# subor.net
KiCad netlist of a schematic drawn in EAGLE
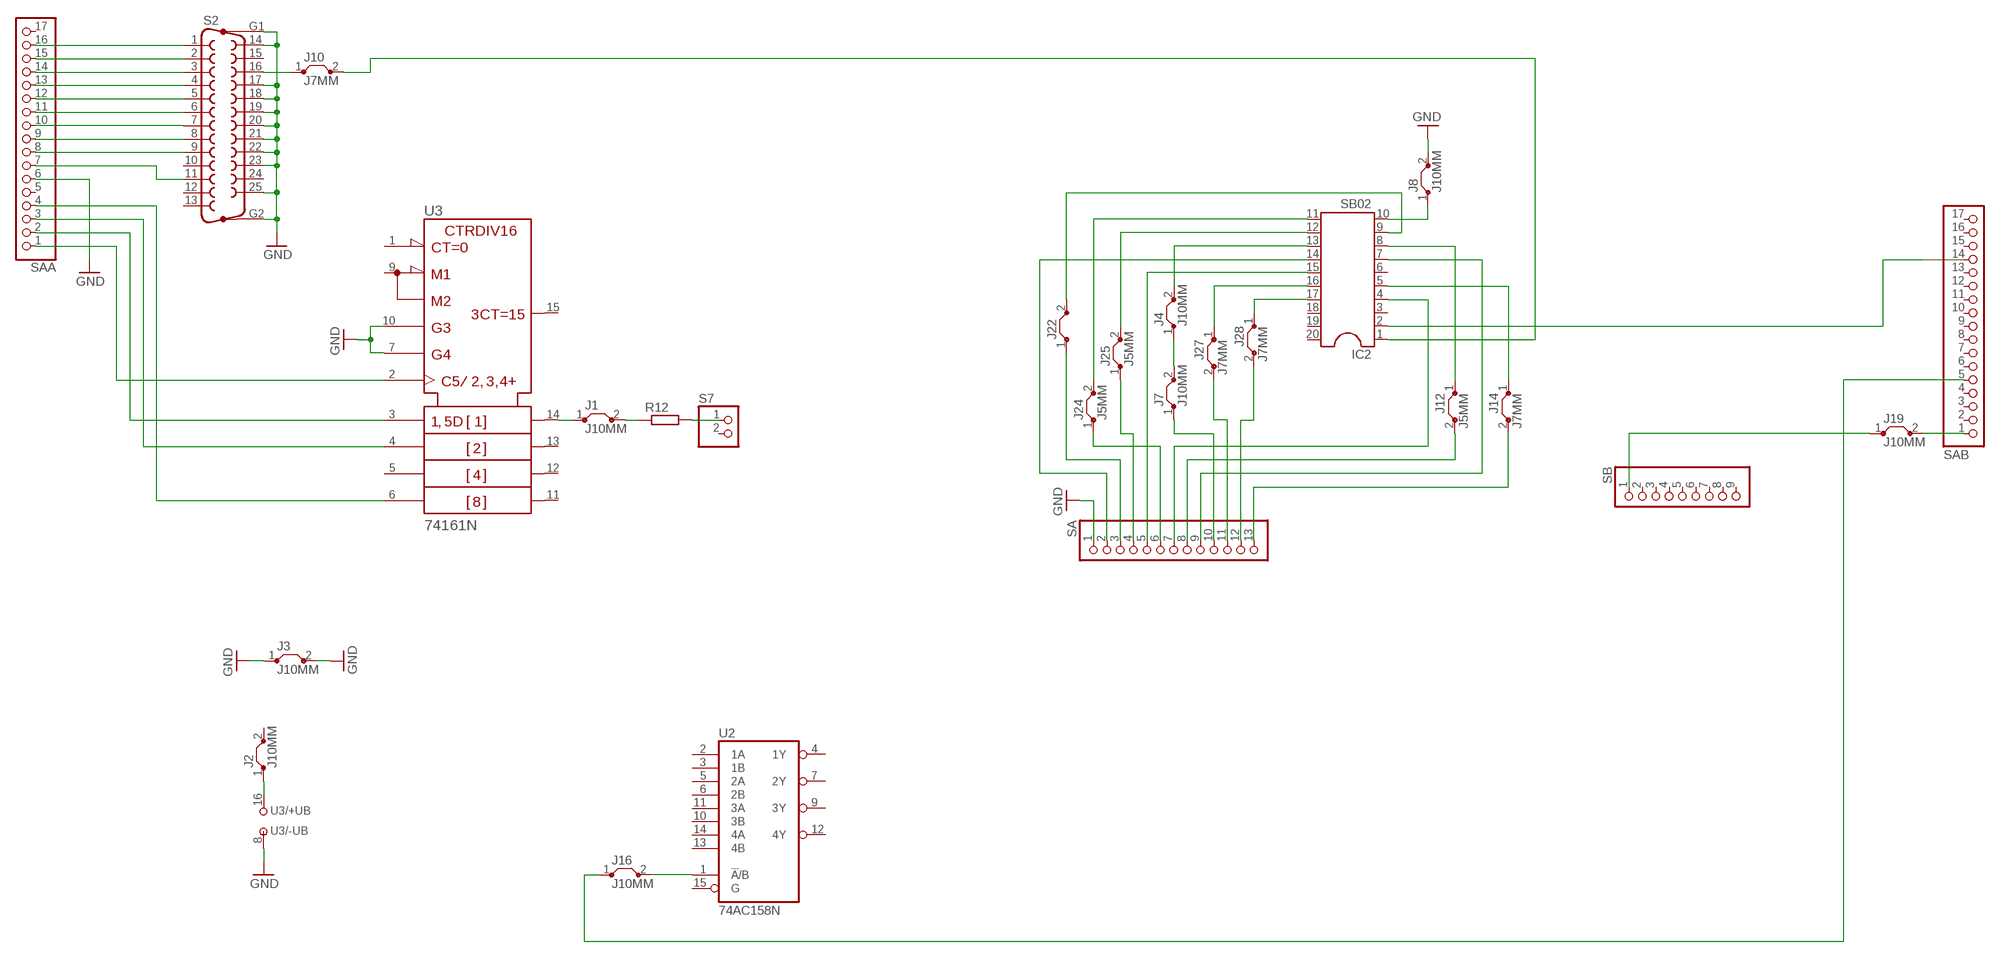
[diagram p0: schematic, sheet 1]

(export (version "E")
  (design (tool "Eeschema 10.0.6"))
  (components
    (comp (ref "IC2")
      (value "SB02")
      (footprint "eagle-import:DIL20")
      (libsource (lib "eagle-import") (part "DIL20"))
    )
    (comp (ref "J1")
      (value "J10MM")
      (footprint "eagle-import:10")
      (libsource (lib "eagle-import") (part "J10MM"))
    )
    (comp (ref "J2")
      (value "J10MM")
      (footprint "eagle-import:10")
      (libsource (lib "eagle-import") (part "J10MM"))
    )
    (comp (ref "J3")
      (value "J10MM")
      (footprint "eagle-import:10")
      (libsource (lib "eagle-import") (part "J10MM"))
    )
    (comp (ref "J4")
      (value "J10MM")
      (footprint "eagle-import:10")
      (libsource (lib "eagle-import") (part "J10MM"))
    )
    (comp (ref "J7")
      (value "J10MM")
      (footprint "eagle-import:10")
      (libsource (lib "eagle-import") (part "J10MM"))
    )
    (comp (ref "J8")
      (value "J10MM")
      (footprint "eagle-import:10")
      (libsource (lib "eagle-import") (part "J10MM"))
    )
    (comp (ref "J10")
      (value "J7MM")
      (footprint "eagle-import:07")
      (libsource (lib "eagle-import") (part "J7MM"))
    )
    (comp (ref "J12")
      (value "J5MM")
      (footprint "eagle-import:05")
      (libsource (lib "eagle-import") (part "J5MM"))
    )
    (comp (ref "J14")
      (value "J7MM")
      (footprint "eagle-import:07")
      (libsource (lib "eagle-import") (part "J7MM"))
    )
    (comp (ref "J16")
      (value "J10MM")
      (footprint "eagle-import:10")
      (libsource (lib "eagle-import") (part "J10MM"))
    )
    (comp (ref "J19")
      (value "J10MM")
      (footprint "eagle-import:10")
      (libsource (lib "eagle-import") (part "J10MM"))
    )
    (comp (ref "J22")
      (value "J10MM")
      (footprint "eagle-import:10")
      (libsource (lib "eagle-import") (part "J10MM"))
    )
    (comp (ref "J24")
      (value "J5MM")
      (footprint "eagle-import:05")
      (libsource (lib "eagle-import") (part "J5MM"))
    )
    (comp (ref "J25")
      (value "J5MM")
      (footprint "eagle-import:05")
      (libsource (lib "eagle-import") (part "J5MM"))
    )
    (comp (ref "J27")
      (value "J7MM")
      (footprint "eagle-import:07")
      (libsource (lib "eagle-import") (part "J7MM"))
    )
    (comp (ref "J28")
      (value "J7MM")
      (footprint "eagle-import:07")
      (libsource (lib "eagle-import") (part "J7MM"))
    )
    (comp (ref "R12")
      (value "R-EU_0207/10")
      (footprint "eagle-import:0207_10")
      (libsource (lib "eagle-import") (part "R-EU_0207/10"))
    )
    (comp (ref "S2")
      (value "F25HP")
      (footprint "eagle-import:F25HP")
      (libsource (lib "eagle-import") (part "F25HP"))
    )
    (comp (ref "S7")
      (value "PINHD-1X2")
      (footprint "eagle-import:1X02")
      (libsource (lib "eagle-import") (part "PINHD-1X2"))
    )
    (comp (ref "SA")
      (value "PINHD-1X13/90")
      (footprint "eagle-import:1X13_90")
      (libsource (lib "eagle-import") (part "PINHD-1X13/90"))
    )
    (comp (ref "SAA")
      (value "PINHD-1X17")
      (footprint "eagle-import:1X17")
      (libsource (lib "eagle-import") (part "PINHD-1X17"))
    )
    (comp (ref "SAB")
      (value "PINHD-1X17")
      (footprint "eagle-import:1X17")
      (libsource (lib "eagle-import") (part "PINHD-1X17"))
    )
    (comp (ref "SB")
      (value "PINHD-1X9/90")
      (footprint "eagle-import:1X09_90")
      (libsource (lib "eagle-import") (part "PINHD-1X9/90"))
    )
    (comp (ref "U2")
      (value "74AC158N")
      (footprint "eagle-import:DIL16")
      (libsource (lib "eagle-import") (part "74158NAC"))
    )
    (comp (ref "U3")
      (value "74161N")
      (footprint "eagle-import:DIL16")
      (libsource (lib "eagle-import") (part "74161N"))
    )
  )
  (nets
    (net (code "1") (name "GND") (class "Default")
      (node (ref "J3") (pin "1") (pinfunction "1_1") (pintype "passive"))
      (node (ref "J3") (pin "2") (pinfunction "2_2") (pintype "passive"))
      (node (ref "J8") (pin "2") (pinfunction "2_2") (pintype "passive"))
      (node (ref "S2") (pin "14") (pinfunction "14_14") (pintype "passive"))
      (node (ref "S2") (pin "17") (pinfunction "17_17") (pintype "passive"))
      (node (ref "S2") (pin "18") (pinfunction "18_18") (pintype "passive"))
      (node (ref "S2") (pin "19") (pinfunction "19_19") (pintype "passive"))
      (node (ref "S2") (pin "20") (pinfunction "20_20") (pintype "passive"))
      (node (ref "S2") (pin "21") (pinfunction "21_21") (pintype "passive"))
      (node (ref "S2") (pin "22") (pinfunction "22_22") (pintype "passive"))
      (node (ref "S2") (pin "23") (pinfunction "23_23") (pintype "passive"))
      (node (ref "S2") (pin "25") (pinfunction "25_25") (pintype "passive"))
      (node (ref "S2") (pin "G1") (pinfunction "G1_G1") (pintype "passive"))
      (node (ref "S2") (pin "G2") (pinfunction "G2_G2") (pintype "passive"))
      (node (ref "SA") (pin "1") (pinfunction "1_1") (pintype "passive"))
      (node (ref "SAA") (pin "6") (pinfunction "6_6") (pintype "passive"))
      (node (ref "U3") (pin "10") (pinfunction "ENT_10") (pintype "input"))
      (node (ref "U3") (pin "7") (pinfunction "ENP_7") (pintype "input"))
      (node (ref "U3") (pin "8") (pinfunction "-UB_8") (pintype "power_in"))
    )
    (net (code "2") (name "Net-(IC2-Pad1)") (class "Default")
      (node (ref "IC2") (pin "1") (pinfunction "1_1") (pintype "passive"))
      (node (ref "J10") (pin "2") (pinfunction "2_2") (pintype "passive"))
    )
    (net (code "3") (name "Net-(IC2-Pad4)") (class "Default")
      (node (ref "IC2") (pin "4") (pinfunction "4_4") (pintype "passive"))
      (node (ref "SA") (pin "7") (pinfunction "7_7") (pintype "passive"))
    )
    (net (code "4") (name "Net-(IC2-Pad5)") (class "Default")
      (node (ref "IC2") (pin "5") (pinfunction "5_5") (pintype "passive"))
      (node (ref "J14") (pin "1") (pinfunction "1_1") (pintype "passive"))
    )
    (net (code "5") (name "Net-(IC2-Pad7)") (class "Default")
      (node (ref "IC2") (pin "7") (pinfunction "7_7") (pintype "passive"))
      (node (ref "SA") (pin "9") (pinfunction "9_9") (pintype "passive"))
    )
    (net (code "6") (name "Net-(IC2-Pad8)") (class "Default")
      (node (ref "IC2") (pin "8") (pinfunction "8_8") (pintype "passive"))
      (node (ref "J12") (pin "1") (pinfunction "1_1") (pintype "passive"))
    )
    (net (code "7") (name "Net-(IC2-Pad9)") (class "Default")
      (node (ref "IC2") (pin "9") (pinfunction "9_9") (pintype "passive"))
      (node (ref "J22") (pin "2") (pinfunction "2_2") (pintype "passive"))
    )
    (net (code "8") (name "Net-(IC2-Pad10)") (class "Default")
      (node (ref "IC2") (pin "10") (pinfunction "10_10") (pintype "passive"))
      (node (ref "J8") (pin "1") (pinfunction "1_1") (pintype "passive"))
    )
    (net (code "9") (name "Net-(IC2-Pad11)") (class "Default")
      (node (ref "IC2") (pin "11") (pinfunction "11_11") (pintype "passive"))
      (node (ref "J24") (pin "2") (pinfunction "2_2") (pintype "passive"))
    )
    (net (code "10") (name "Net-(IC2-Pad12)") (class "Default")
      (node (ref "IC2") (pin "12") (pinfunction "12_12") (pintype "passive"))
      (node (ref "J25") (pin "2") (pinfunction "2_2") (pintype "passive"))
    )
    (net (code "11") (name "Net-(IC2-Pad13)") (class "Default")
      (node (ref "IC2") (pin "13") (pinfunction "13_13") (pintype "passive"))
      (node (ref "J4") (pin "2") (pinfunction "2_2") (pintype "passive"))
    )
    (net (code "12") (name "Net-(IC2-Pad14)") (class "Default")
      (node (ref "IC2") (pin "14") (pinfunction "14_14") (pintype "passive"))
      (node (ref "SA") (pin "2") (pinfunction "2_2") (pintype "passive"))
    )
    (net (code "13") (name "Net-(IC2-Pad15)") (class "Default")
      (node (ref "IC2") (pin "15") (pinfunction "15_15") (pintype "passive"))
      (node (ref "SA") (pin "5") (pinfunction "5_5") (pintype "passive"))
    )
    (net (code "14") (name "Net-(IC2-Pad16)") (class "Default")
      (node (ref "IC2") (pin "16") (pinfunction "16_16") (pintype "passive"))
      (node (ref "J27") (pin "1") (pinfunction "1_1") (pintype "passive"))
    )
    (net (code "15") (name "Net-(IC2-Pad17)") (class "Default")
      (node (ref "IC2") (pin "17") (pinfunction "17_17") (pintype "passive"))
      (node (ref "J28") (pin "1") (pinfunction "1_1") (pintype "passive"))
    )
    (net (code "16") (name "Net-(J1-Pad2)") (class "Default")
      (node (ref "J1") (pin "2") (pinfunction "2_2") (pintype "passive"))
      (node (ref "R12") (pin "1") (pinfunction "1_1") (pintype "passive"))
    )
    (net (code "17") (name "Net-(J4-Pad1)") (class "Default")
      (node (ref "J4") (pin "1") (pinfunction "1_1") (pintype "passive"))
      (node (ref "J7") (pin "2") (pinfunction "2_2") (pintype "passive"))
    )
    (net (code "18") (name "Net-(J7-Pad1)") (class "Default")
      (node (ref "J7") (pin "1") (pinfunction "1_1") (pintype "passive"))
      (node (ref "SA") (pin "10") (pinfunction "10_10") (pintype "passive"))
    )
    (net (code "19") (name "Net-(J10-Pad1)") (class "Default")
      (node (ref "J10") (pin "1") (pinfunction "1_1") (pintype "passive"))
      (node (ref "S2") (pin "16") (pinfunction "16_16") (pintype "passive"))
    )
    (net (code "20") (name "Net-(J12-Pad2)") (class "Default")
      (node (ref "J12") (pin "2") (pinfunction "2_2") (pintype "passive"))
      (node (ref "SA") (pin "8") (pinfunction "8_8") (pintype "passive"))
    )
    (net (code "21") (name "Net-(J14-Pad2)") (class "Default")
      (node (ref "J14") (pin "2") (pinfunction "2_2") (pintype "passive"))
      (node (ref "SA") (pin "13") (pinfunction "13_13") (pintype "passive"))
    )
    (net (code "22") (name "Net-(J16-Pad1)") (class "Default")
      (node (ref "J16") (pin "1") (pinfunction "1_1") (pintype "passive"))
      (node (ref "SAB") (pin "5") (pinfunction "5_5") (pintype "passive"))
    )
    (net (code "23") (name "Net-(J19-Pad1)") (class "Default")
      (node (ref "J19") (pin "1") (pinfunction "1_1") (pintype "passive"))
      (node (ref "SB") (pin "1") (pinfunction "1_1") (pintype "passive"))
    )
    (net (code "24") (name "Net-(J19-Pad2)") (class "Default")
      (node (ref "J19") (pin "2") (pinfunction "2_2") (pintype "passive"))
      (node (ref "SAB") (pin "1") (pinfunction "1_1") (pintype "passive"))
    )
    (net (code "25") (name "Net-(J22-Pad1)") (class "Default")
      (node (ref "J22") (pin "1") (pinfunction "1_1") (pintype "passive"))
      (node (ref "SA") (pin "3") (pinfunction "3_3") (pintype "passive"))
    )
    (net (code "26") (name "Net-(J24-Pad1)") (class "Default")
      (node (ref "J24") (pin "1") (pinfunction "1_1") (pintype "passive"))
      (node (ref "SA") (pin "6") (pinfunction "6_6") (pintype "passive"))
    )
    (net (code "27") (name "Net-(J25-Pad1)") (class "Default")
      (node (ref "J25") (pin "1") (pinfunction "1_1") (pintype "passive"))
      (node (ref "SA") (pin "4") (pinfunction "4_4") (pintype "passive"))
    )
    (net (code "28") (name "Net-(J27-Pad2)") (class "Default")
      (node (ref "J27") (pin "2") (pinfunction "2_2") (pintype "passive"))
      (node (ref "SA") (pin "11") (pinfunction "11_11") (pintype "passive"))
    )
    (net (code "29") (name "Net-(J28-Pad2)") (class "Default")
      (node (ref "J28") (pin "2") (pinfunction "2_2") (pintype "passive"))
      (node (ref "SA") (pin "12") (pinfunction "12_12") (pintype "passive"))
    )
    (net (code "30") (name "Net-(R12-Pad2)") (class "Default")
      (node (ref "R12") (pin "2") (pinfunction "2_2") (pintype "passive"))
      (node (ref "S7") (pin "1") (pinfunction "1_1") (pintype "passive"))
    )
    (net (code "31") (name "Net-(S2-Pad1)") (class "Default")
      (node (ref "S2") (pin "1") (pinfunction "1_1") (pintype "passive"))
      (node (ref "SAA") (pin "16") (pinfunction "16_16") (pintype "passive"))
    )
    (net (code "32") (name "Net-(S2-Pad2)") (class "Default")
      (node (ref "S2") (pin "2") (pinfunction "2_2") (pintype "passive"))
      (node (ref "SAA") (pin "15") (pinfunction "15_15") (pintype "passive"))
    )
    (net (code "33") (name "Net-(S2-Pad3)") (class "Default")
      (node (ref "S2") (pin "3") (pinfunction "3_3") (pintype "passive"))
      (node (ref "SAA") (pin "14") (pinfunction "14_14") (pintype "passive"))
    )
    (net (code "34") (name "Net-(S2-Pad4)") (class "Default")
      (node (ref "S2") (pin "4") (pinfunction "4_4") (pintype "passive"))
      (node (ref "SAA") (pin "13") (pinfunction "13_13") (pintype "passive"))
    )
    (net (code "35") (name "Net-(S2-Pad5)") (class "Default")
      (node (ref "S2") (pin "5") (pinfunction "5_5") (pintype "passive"))
      (node (ref "SAA") (pin "12") (pinfunction "12_12") (pintype "passive"))
    )
    (net (code "36") (name "Net-(S2-Pad6)") (class "Default")
      (node (ref "S2") (pin "6") (pinfunction "6_6") (pintype "passive"))
      (node (ref "SAA") (pin "11") (pinfunction "11_11") (pintype "passive"))
    )
    (net (code "37") (name "Net-(S2-Pad7)") (class "Default")
      (node (ref "S2") (pin "7") (pinfunction "7_7") (pintype "passive"))
      (node (ref "SAA") (pin "10") (pinfunction "10_10") (pintype "passive"))
    )
    (net (code "38") (name "Net-(S2-Pad8)") (class "Default")
      (node (ref "S2") (pin "8") (pinfunction "8_8") (pintype "passive"))
      (node (ref "SAA") (pin "9") (pinfunction "9_9") (pintype "passive"))
    )
    (net (code "39") (name "Net-(S2-Pad9)") (class "Default")
      (node (ref "S2") (pin "9") (pinfunction "9_9") (pintype "passive"))
      (node (ref "SAA") (pin "8") (pinfunction "8_8") (pintype "passive"))
    )
    (net (code "40") (name "Net-(S2-Pad11)") (class "Default")
      (node (ref "S2") (pin "11") (pinfunction "11_11") (pintype "passive"))
      (node (ref "SAA") (pin "7") (pinfunction "7_7") (pintype "passive"))
    )
    (net (code "41") (name "Net-(U2A-~{A}{slash}B)") (class "Default")
      (node (ref "J16") (pin "2") (pinfunction "2_2") (pintype "passive"))
      (node (ref "U2") (pin "1") (pinfunction "~{A}/B_1") (pintype "input"))
    )
    (net (code "42") (name "Net-(U3A-+UB)") (class "Default")
      (node (ref "J2") (pin "1") (pinfunction "1_1") (pintype "passive"))
      (node (ref "U3") (pin "16") (pinfunction "+UB_16") (pintype "power_in"))
    )
    (net (code "43") (name "Net-(U3C-A)") (class "Default")
      (node (ref "SAA") (pin "2") (pinfunction "2_2") (pintype "passive"))
      (node (ref "U3") (pin "3") (pinfunction "A_3") (pintype "input"))
    )
    (net (code "44") (name "Net-(U3C-B)") (class "Default")
      (node (ref "SAA") (pin "3") (pinfunction "3_3") (pintype "passive"))
      (node (ref "U3") (pin "4") (pinfunction "B_4") (pintype "input"))
    )
    (net (code "45") (name "Net-(U3C-CLK)") (class "Default")
      (node (ref "SAA") (pin "1") (pinfunction "1_1") (pintype "passive"))
      (node (ref "U3") (pin "2") (pinfunction "CLK_2") (pintype "input"))
    )
    (net (code "46") (name "Net-(U3C-D)") (class "Default")
      (node (ref "SAA") (pin "4") (pinfunction "4_4") (pintype "passive"))
      (node (ref "U3") (pin "6") (pinfunction "D_6") (pintype "input"))
    )
    (net (code "47") (name "Net-(U3C-QA)") (class "Default")
      (node (ref "J1") (pin "1") (pinfunction "1_1") (pintype "passive"))
      (node (ref "U3") (pin "14") (pinfunction "QA_14") (pintype "output"))
    )
    (net (code "48") (name "unconnected-(IC2-Pad2)") (class "Default")
      (node (ref "IC2") (pin "2") (pinfunction "2_2") (pintype "passive"))
    )
    (net (code "49") (name "unconnected-(IC2-Pad3)") (class "Default")
      (node (ref "IC2") (pin "3") (pinfunction "3_3") (pintype "passive"))
    )
    (net (code "50") (name "unconnected-(IC2-Pad6)") (class "Default")
      (node (ref "IC2") (pin "6") (pinfunction "6_6") (pintype "passive"))
    )
    (net (code "51") (name "unconnected-(IC2-Pad18)") (class "Default")
      (node (ref "IC2") (pin "18") (pinfunction "18_18") (pintype "passive"))
    )
    (net (code "52") (name "unconnected-(IC2-Pad19)") (class "Default")
      (node (ref "IC2") (pin "19") (pinfunction "19_19") (pintype "passive"))
    )
    (net (code "53") (name "unconnected-(IC2-Pad20)") (class "Default")
      (node (ref "IC2") (pin "20") (pinfunction "20_20") (pintype "passive"))
    )
    (net (code "54") (name "unconnected-(J2-Pad2)") (class "Default")
      (node (ref "J2") (pin "2") (pinfunction "2_2") (pintype "passive"))
    )
    (net (code "55") (name "unconnected-(S2-Pad10)") (class "Default")
      (node (ref "S2") (pin "10") (pinfunction "10_10") (pintype "passive"))
    )
    (net (code "56") (name "unconnected-(S2-Pad12)") (class "Default")
      (node (ref "S2") (pin "12") (pinfunction "12_12") (pintype "passive"))
    )
    (net (code "57") (name "unconnected-(S2-Pad13)") (class "Default")
      (node (ref "S2") (pin "13") (pinfunction "13_13") (pintype "passive"))
    )
    (net (code "58") (name "unconnected-(S2-Pad15)") (class "Default")
      (node (ref "S2") (pin "15") (pinfunction "15_15") (pintype "passive"))
    )
    (net (code "59") (name "unconnected-(S2-Pad24)") (class "Default")
      (node (ref "S2") (pin "24") (pinfunction "24_24") (pintype "passive"))
    )
    (net (code "60") (name "unconnected-(S7-Pad2)") (class "Default")
      (node (ref "S7") (pin "2") (pinfunction "2_2") (pintype "passive"))
    )
    (net (code "61") (name "unconnected-(SAA-Pad5)") (class "Default")
      (node (ref "SAA") (pin "5") (pinfunction "5_5") (pintype "passive"))
    )
    (net (code "62") (name "unconnected-(SAA-Pad17)") (class "Default")
      (node (ref "SAA") (pin "17") (pinfunction "17_17") (pintype "passive"))
    )
    (net (code "63") (name "unconnected-(SAB-Pad2)") (class "Default")
      (node (ref "SAB") (pin "2") (pinfunction "2_2") (pintype "passive"))
    )
    (net (code "64") (name "unconnected-(SAB-Pad3)") (class "Default")
      (node (ref "SAB") (pin "3") (pinfunction "3_3") (pintype "passive"))
    )
    (net (code "65") (name "unconnected-(SAB-Pad4)") (class "Default")
      (node (ref "SAB") (pin "4") (pinfunction "4_4") (pintype "passive"))
    )
    (net (code "66") (name "unconnected-(SAB-Pad6)") (class "Default")
      (node (ref "SAB") (pin "6") (pinfunction "6_6") (pintype "passive"))
    )
    (net (code "67") (name "unconnected-(SAB-Pad7)") (class "Default")
      (node (ref "SAB") (pin "7") (pinfunction "7_7") (pintype "passive"))
    )
    (net (code "68") (name "unconnected-(SAB-Pad8)") (class "Default")
      (node (ref "SAB") (pin "8") (pinfunction "8_8") (pintype "passive"))
    )
    (net (code "69") (name "unconnected-(SAB-Pad9)") (class "Default")
      (node (ref "SAB") (pin "9") (pinfunction "9_9") (pintype "passive"))
    )
    (net (code "70") (name "unconnected-(SAB-Pad10)") (class "Default")
      (node (ref "SAB") (pin "10") (pinfunction "10_10") (pintype "passive"))
    )
    (net (code "71") (name "unconnected-(SAB-Pad11)") (class "Default")
      (node (ref "SAB") (pin "11") (pinfunction "11_11") (pintype "passive"))
    )
    (net (code "72") (name "unconnected-(SAB-Pad12)") (class "Default")
      (node (ref "SAB") (pin "12") (pinfunction "12_12") (pintype "passive"))
    )
    (net (code "73") (name "unconnected-(SAB-Pad13)") (class "Default")
      (node (ref "SAB") (pin "13") (pinfunction "13_13") (pintype "passive"))
    )
    (net (code "74") (name "unconnected-(SAB-Pad14)") (class "Default")
      (node (ref "SAB") (pin "14") (pinfunction "14_14") (pintype "passive"))
    )
    (net (code "75") (name "unconnected-(SAB-Pad15)") (class "Default")
      (node (ref "SAB") (pin "15") (pinfunction "15_15") (pintype "passive"))
    )
    (net (code "76") (name "unconnected-(SAB-Pad16)") (class "Default")
      (node (ref "SAB") (pin "16") (pinfunction "16_16") (pintype "passive"))
    )
    (net (code "77") (name "unconnected-(SAB-Pad17)") (class "Default")
      (node (ref "SAB") (pin "17") (pinfunction "17_17") (pintype "passive"))
    )
    (net (code "78") (name "unconnected-(SB-Pad2)") (class "Default")
      (node (ref "SB") (pin "2") (pinfunction "2_2") (pintype "passive"))
    )
    (net (code "79") (name "unconnected-(SB-Pad3)") (class "Default")
      (node (ref "SB") (pin "3") (pinfunction "3_3") (pintype "passive"))
    )
    (net (code "80") (name "unconnected-(SB-Pad4)") (class "Default")
      (node (ref "SB") (pin "4") (pinfunction "4_4") (pintype "passive"))
    )
    (net (code "81") (name "unconnected-(SB-Pad5)") (class "Default")
      (node (ref "SB") (pin "5") (pinfunction "5_5") (pintype "passive"))
    )
    (net (code "82") (name "unconnected-(SB-Pad6)") (class "Default")
      (node (ref "SB") (pin "6") (pinfunction "6_6") (pintype "passive"))
    )
    (net (code "83") (name "unconnected-(SB-Pad7)") (class "Default")
      (node (ref "SB") (pin "7") (pinfunction "7_7") (pintype "passive"))
    )
    (net (code "84") (name "unconnected-(SB-Pad8)") (class "Default")
      (node (ref "SB") (pin "8") (pinfunction "8_8") (pintype "passive"))
    )
    (net (code "85") (name "unconnected-(SB-Pad9)") (class "Default")
      (node (ref "SB") (pin "9") (pinfunction "9_9") (pintype "passive"))
    )
    (net (code "86") (name "unconnected-(U2A-1A-Pad2)") (class "Default")
      (node (ref "U2") (pin "2") (pinfunction "1A_2") (pintype "input"))
    )
    (net (code "87") (name "unconnected-(U2A-1B-Pad3)") (class "Default")
      (node (ref "U2") (pin "3") (pinfunction "1B_3") (pintype "input"))
    )
    (net (code "88") (name "unconnected-(U2A-1Y-Pad4)") (class "Default")
      (node (ref "U2") (pin "4") (pinfunction "1Y_4") (pintype "output"))
    )
    (net (code "89") (name "unconnected-(U2A-2A-Pad5)") (class "Default")
      (node (ref "U2") (pin "5") (pinfunction "2A_5") (pintype "input"))
    )
    (net (code "90") (name "unconnected-(U2A-2B-Pad6)") (class "Default")
      (node (ref "U2") (pin "6") (pinfunction "2B_6") (pintype "input"))
    )
    (net (code "91") (name "unconnected-(U2A-2Y-Pad7)") (class "Default")
      (node (ref "U2") (pin "7") (pinfunction "2Y_7") (pintype "output"))
    )
    (net (code "92") (name "unconnected-(U2A-3A-Pad11)") (class "Default")
      (node (ref "U2") (pin "11") (pinfunction "3A_11") (pintype "input"))
    )
    (net (code "93") (name "unconnected-(U2A-3B-Pad10)") (class "Default")
      (node (ref "U2") (pin "10") (pinfunction "3B_10") (pintype "input"))
    )
    (net (code "94") (name "unconnected-(U2A-3Y-Pad9)") (class "Default")
      (node (ref "U2") (pin "9") (pinfunction "3Y_9") (pintype "output"))
    )
    (net (code "95") (name "unconnected-(U2A-4A-Pad14)") (class "Default")
      (node (ref "U2") (pin "14") (pinfunction "4A_14") (pintype "input"))
    )
    (net (code "96") (name "unconnected-(U2A-4B-Pad13)") (class "Default")
      (node (ref "U2") (pin "13") (pinfunction "4B_13") (pintype "input"))
    )
    (net (code "97") (name "unconnected-(U2A-4Y-Pad12)") (class "Default")
      (node (ref "U2") (pin "12") (pinfunction "4Y_12") (pintype "output"))
    )
    (net (code "98") (name "unconnected-(U2A-G-Pad15)") (class "Default")
      (node (ref "U2") (pin "15") (pinfunction "G_15") (pintype "input"))
    )
    (net (code "99") (name "unconnected-(U3C-C-Pad5)") (class "Default")
      (node (ref "U3") (pin "5") (pinfunction "C_5") (pintype "input"))
    )
    (net (code "100") (name "unconnected-(U3C-QB-Pad13)") (class "Default")
      (node (ref "U3") (pin "13") (pinfunction "QB_13") (pintype "output"))
    )
    (net (code "101") (name "unconnected-(U3C-QC-Pad12)") (class "Default")
      (node (ref "U3") (pin "12") (pinfunction "QC_12") (pintype "output"))
    )
    (net (code "102") (name "unconnected-(U3C-QD-Pad11)") (class "Default")
      (node (ref "U3") (pin "11") (pinfunction "QD_11") (pintype "output"))
    )
    (net (code "103") (name "unconnected-(U3C-RCO-Pad15)") (class "Default")
      (node (ref "U3") (pin "15") (pinfunction "RCO_15") (pintype "output"))
    )
    (net (code "104") (name "unconnected-(U3C-~{CLR}-Pad1)") (class "Default")
      (node (ref "U3") (pin "1") (pinfunction "~{CLR}_1") (pintype "input"))
    )
    (net (code "105") (name "unconnected-(U3C-~{LOAD}-Pad9)") (class "Default")
      (node (ref "U3") (pin "9") (pinfunction "~{LOAD}_9") (pintype "input"))
    )
  )
)
